# First_Draft.net
KiCad netlist of a schematic drawn in EAGLE
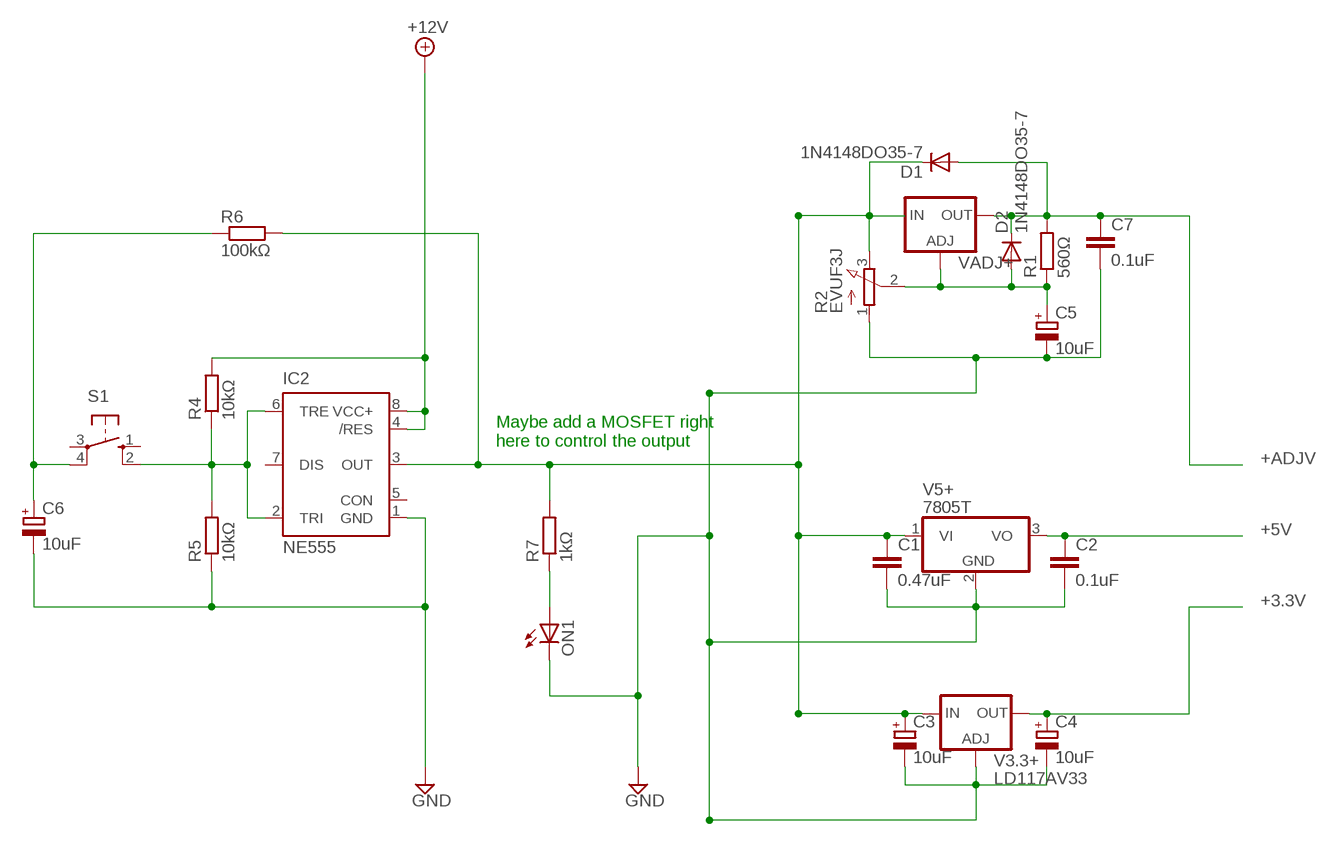
[diagram p0: schematic, sheet 1]

(export (version "E")
  (design (tool "Eeschema 10.0.6"))
  (components
    (comp (ref "C1")
      (value "0.47uF")
      (footprint "eagle-import:C025-025X050")
      (libsource (lib "eagle-import") (part "C-EU025-025X050"))
    )
    (comp (ref "C2")
      (value "0.1uF")
      (footprint "eagle-import:C025-025X050")
      (libsource (lib "eagle-import") (part "C-EU025-025X050"))
    )
    (comp (ref "C3")
      (value "10uF")
      (footprint "eagle-import:E2,5-6")
      (libsource (lib "eagle-import") (part "CPOL-EUE2.5-6"))
    )
    (comp (ref "C4")
      (value "10uF")
      (footprint "eagle-import:E2,5-6")
      (libsource (lib "eagle-import") (part "CPOL-EUE2.5-6"))
    )
    (comp (ref "C5")
      (value "10uF")
      (footprint "eagle-import:E2,5-6")
      (libsource (lib "eagle-import") (part "CPOL-EUE2.5-6"))
    )
    (comp (ref "C6")
      (value "10uF")
      (footprint "eagle-import:E2,5-6")
      (libsource (lib "eagle-import") (part "CPOL-EUE2.5-6"))
    )
    (comp (ref "C7")
      (value "0.1uF")
      (footprint "eagle-import:C025-025X050")
      (libsource (lib "eagle-import") (part "C-EU025-025X050"))
    )
    (comp (ref "D1")
      (value "1N4148DO35-7")
      (footprint "eagle-import:DO35-7")
      (libsource (lib "eagle-import") (part "1N4148DO35-7"))
    )
    (comp (ref "D2")
      (value "1N4148DO35-7")
      (footprint "eagle-import:DO35-7")
      (libsource (lib "eagle-import") (part "1N4148DO35-7"))
    )
    (comp (ref "IC2")
      (value "NE555")
      (footprint "eagle-import:DIL-08")
      (fields (field (name "MF") "Arrow Electronics") (field (name "MPN") "NE555N"))
      (libsource (lib "eagle-import") (part "NE555"))
    )
    (comp (ref "ON1")
      (value "LED3MM")
      (footprint "eagle-import:LED3MM")
      (libsource (lib "eagle-import") (part "LED3MM"))
    )
    (comp (ref "R1")
      (value "560Ω")
      (footprint "eagle-import:0207_10")
      (libsource (lib "eagle-import") (part "resistor_R-EU_0207/10"))
    )
    (comp (ref "R2")
      (value "EVUF3J")
      (footprint "eagle-import:EVUFXJ")
      (libsource (lib "eagle-import") (part "EVUF3J"))
    )
    (comp (ref "R4")
      (value "10kΩ")
      (footprint "eagle-import:0207_10")
      (libsource (lib "eagle-import") (part "R-EU_0207/10"))
    )
    (comp (ref "R5")
      (value "10kΩ")
      (footprint "eagle-import:0207_10")
      (libsource (lib "eagle-import") (part "R-EU_0207/10"))
    )
    (comp (ref "R6")
      (value "100kΩ")
      (footprint "eagle-import:0207_10")
      (libsource (lib "eagle-import") (part "R-EU_0207/10"))
    )
    (comp (ref "R7")
      (value "1kΩ")
      (footprint "eagle-import:0207_10")
      (libsource (lib "eagle-import") (part "R-EU_0207/10"))
    )
    (comp (ref "S1")
      (value "10-XX")
      (footprint "eagle-import:B3F-10XX")
      (fields (field (name "MPN") "B3F-1000"))
      (libsource (lib "eagle-import") (part "10-XX"))
    )
    (comp (ref "V3.3+")
      (value "LD117AV33")
      (footprint "eagle-import:TO220L1")
      (libsource (lib "eagle-import") (part "LD117A?V33"))
    )
    (comp (ref "V5+")
      (value "7805T")
      (footprint "eagle-import:TO220H")
      (libsource (lib "eagle-import") (part "78T05"))
    )
    (comp (ref "VADJ+")
      (value "LM317TL")
      (footprint "eagle-import:317TL")
      (libsource (lib "eagle-import") (part "LM317TL"))
    )
  )
  (nets
    (net (code "1") (name "+12V") (class "Default")
      (node (ref "IC2") (pin "4") (pinfunction "/RES_4") (pintype "input"))
      (node (ref "IC2") (pin "8") (pinfunction "VCC+_8") (pintype "power_in"))
      (node (ref "R4") (pin "2") (pinfunction "2_2") (pintype "passive"))
    )
    (net (code "2") (name "/+3.3V") (class "Default")
      (node (ref "C4") (pin "+") (pinfunction "+_+") (pintype "passive"))
      (node (ref "V3.3+") (pin "2") (pinfunction "OUT_2") (pintype "passive"))
    )
    (net (code "3") (name "/+5V") (class "Default")
      (node (ref "C2") (pin "1") (pinfunction "1_1") (pintype "passive"))
      (node (ref "V5+") (pin "3") (pinfunction "VO_3") (pintype "passive"))
    )
    (net (code "4") (name "/+ADJV") (class "Default")
      (node (ref "C7") (pin "1") (pinfunction "1_1") (pintype "passive"))
      (node (ref "D1") (pin "A") (pinfunction "A_A") (pintype "passive"))
      (node (ref "D2") (pin "C") (pinfunction "C_C") (pintype "passive"))
      (node (ref "R1") (pin "2") (pinfunction "2_2") (pintype "passive"))
      (node (ref "VADJ+") (pin "2") (pinfunction "OUT_2") (pintype "passive"))
    )
    (net (code "5") (name "GND") (class "Default")
      (node (ref "C1") (pin "2") (pinfunction "2_2") (pintype "passive"))
      (node (ref "C2") (pin "2") (pinfunction "2_2") (pintype "passive"))
      (node (ref "C3") (pin "-") (pinfunction "-_-") (pintype "passive"))
      (node (ref "C4") (pin "-") (pinfunction "-_-") (pintype "passive"))
      (node (ref "C5") (pin "-") (pinfunction "-_-") (pintype "passive"))
      (node (ref "C6") (pin "-") (pinfunction "-_-") (pintype "passive"))
      (node (ref "C7") (pin "2") (pinfunction "2_2") (pintype "passive"))
      (node (ref "IC2") (pin "1") (pinfunction "GND_1") (pintype "power_in"))
      (node (ref "ON1") (pin "K") (pinfunction "C_K") (pintype "passive"))
      (node (ref "R2") (pin "1") (pinfunction "A_1") (pintype "passive"))
      (node (ref "R5") (pin "1") (pinfunction "1_1") (pintype "passive"))
      (node (ref "V3.3+") (pin "1") (pinfunction "ADJ_1") (pintype "input"))
      (node (ref "V5+") (pin "2") (pinfunction "GND_2") (pintype "passive"))
    )
    (net (code "6") (name "Net-(IC2-OUT)") (class "Default")
      (node (ref "C1") (pin "1") (pinfunction "1_1") (pintype "passive"))
      (node (ref "C3") (pin "+") (pinfunction "+_+") (pintype "passive"))
      (node (ref "D1") (pin "C") (pinfunction "C_C") (pintype "passive"))
      (node (ref "IC2") (pin "3") (pinfunction "OUT_3") (pintype "output"))
      (node (ref "R2") (pin "3") (pinfunction "E_3") (pintype "passive"))
      (node (ref "R6") (pin "2") (pinfunction "2_2") (pintype "passive"))
      (node (ref "R7") (pin "2") (pinfunction "2_2") (pintype "passive"))
      (node (ref "V3.3+") (pin "3") (pinfunction "IN_3") (pintype "input"))
      (node (ref "V5+") (pin "1") (pinfunction "VI_1") (pintype "input"))
      (node (ref "VADJ+") (pin "3") (pinfunction "IN_3") (pintype "input"))
    )
    (net (code "7") (name "Net-(IC2-TRE)") (class "Default")
      (node (ref "IC2") (pin "2") (pinfunction "TRI_2") (pintype "input"))
      (node (ref "IC2") (pin "6") (pinfunction "TRE_6") (pintype "input"))
      (node (ref "R4") (pin "1") (pinfunction "1_1") (pintype "passive"))
      (node (ref "R5") (pin "2") (pinfunction "2_2") (pintype "passive"))
      (node (ref "S1") (pin "2") (pinfunction "S1_2") (pintype "passive"))
    )
    (net (code "8") (name "Net-(ON1-PadA)") (class "Default")
      (node (ref "ON1") (pin "A") (pinfunction "A_A") (pintype "passive"))
      (node (ref "R7") (pin "1") (pinfunction "1_1") (pintype "passive"))
    )
    (net (code "9") (name "Net-(R2-S)") (class "Default")
      (node (ref "C5") (pin "+") (pinfunction "+_+") (pintype "passive"))
      (node (ref "D2") (pin "A") (pinfunction "A_A") (pintype "passive"))
      (node (ref "R1") (pin "1") (pinfunction "1_1") (pintype "passive"))
      (node (ref "R2") (pin "2") (pinfunction "S_2") (pintype "passive"))
      (node (ref "VADJ+") (pin "1") (pinfunction "ADJ_1") (pintype "input"))
    )
    (net (code "10") (name "Net-(S1-P1)") (class "Default")
      (node (ref "C6") (pin "+") (pinfunction "+_+") (pintype "passive"))
      (node (ref "R6") (pin "1") (pinfunction "1_1") (pintype "passive"))
      (node (ref "S1") (pin "4") (pinfunction "P1_4") (pintype "passive"))
    )
    (net (code "11") (name "unconnected-(IC2-CON-Pad5)") (class "Default")
      (node (ref "IC2") (pin "5") (pinfunction "CON_5") (pintype "input"))
    )
    (net (code "12") (name "unconnected-(IC2-DIS-Pad7)") (class "Default")
      (node (ref "IC2") (pin "7") (pinfunction "DIS_7") (pintype "input"))
    )
    (net (code "13") (name "unconnected-(S1-P-Pad3)") (class "Default")
      (node (ref "S1") (pin "3") (pinfunction "P_3") (pintype "passive"))
    )
    (net (code "14") (name "unconnected-(S1-S-Pad1)") (class "Default")
      (node (ref "S1") (pin "1") (pinfunction "S_1") (pintype "passive"))
    )
  )
)
